# main.net
KiCad netlist of a schematic drawn in EAGLE
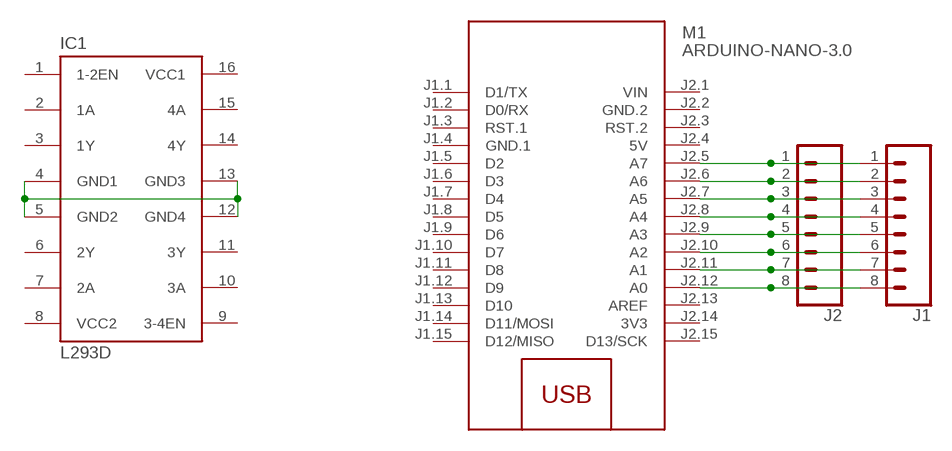
[diagram p0: schematic, sheet 1]

(export (version "E")
  (design (tool "Eeschema 10.0.6"))
  (components
    (comp (ref "IC1")
      (value "L293D")
      (footprint "eagle-import:DIL16")
      (libsource (lib "eagle-import") (part "L293D"))
    )
    (comp (ref "J1")
      (value "CONN_08LONGPADS")
      (footprint "eagle-import:1X08_LONGPADS")
      (libsource (lib "eagle-import") (part "CONN_08LONGPADS"))
    )
    (comp (ref "J2")
      (value "CONN_08LONGPADS")
      (footprint "eagle-import:1X08_LONGPADS")
      (libsource (lib "eagle-import") (part "CONN_08LONGPADS"))
    )
    (comp (ref "M1")
      (value "ARDUINO-NANO-3.0")
      (footprint "eagle-import:ARDUINO-NANO-3.0")
      (libsource (lib "eagle-import") (part "ARDUINO-NANO-3.0"))
    )
  )
  (nets
    (net (code "1") (name "/3V3") (class "Default")
      (node (ref "M1") (pin "J2.14") (pinfunction "3V3_J2.14") (pintype "power_in"))
    )
    (net (code "2") (name "/5V") (class "Default")
      (node (ref "M1") (pin "J2.4") (pinfunction "5V_J2.4") (pintype "power_in"))
    )
    (net (code "3") (name "/GND.1") (class "Default")
      (node (ref "M1") (pin "J1.4") (pinfunction "GND.1_J1.4") (pintype "power_in"))
    )
    (net (code "4") (name "/GND.2") (class "Default")
      (node (ref "M1") (pin "J2.2") (pinfunction "GND.2_J2.2") (pintype "power_in"))
    )
    (net (code "5") (name "/VCC1") (class "Default")
      (node (ref "IC1") (pin "16") (pinfunction "VCC1_16") (pintype "power_in"))
    )
    (net (code "6") (name "/VCC2") (class "Default")
      (node (ref "IC1") (pin "8") (pinfunction "VCC2_8") (pintype "power_in"))
    )
    (net (code "7") (name "/VIN") (class "Default")
      (node (ref "M1") (pin "J2.1") (pinfunction "VIN_J2.1") (pintype "power_in"))
    )
    (net (code "8") (name "Net-(IC1-GND1)") (class "Default")
      (node (ref "IC1") (pin "12") (pinfunction "GND4_12") (pintype "power_in"))
      (node (ref "IC1") (pin "13") (pinfunction "GND3_13") (pintype "power_in"))
      (node (ref "IC1") (pin "4") (pinfunction "GND1_4") (pintype "power_in"))
      (node (ref "IC1") (pin "5") (pinfunction "GND2_5") (pintype "power_in"))
    )
    (net (code "9") (name "Net-(M1-A0)") (class "Default")
      (node (ref "J1") (pin "8") (pinfunction "8_8") (pintype "passive"))
      (node (ref "J2") (pin "8") (pinfunction "8_8") (pintype "passive"))
      (node (ref "M1") (pin "J2.12") (pinfunction "A0_J2.12") (pintype "bidirectional"))
    )
    (net (code "10") (name "Net-(M1-A1)") (class "Default")
      (node (ref "J1") (pin "7") (pinfunction "7_7") (pintype "passive"))
      (node (ref "J2") (pin "7") (pinfunction "7_7") (pintype "passive"))
      (node (ref "M1") (pin "J2.11") (pinfunction "A1_J2.11") (pintype "bidirectional"))
    )
    (net (code "11") (name "Net-(M1-A2)") (class "Default")
      (node (ref "J1") (pin "6") (pinfunction "6_6") (pintype "passive"))
      (node (ref "J2") (pin "6") (pinfunction "6_6") (pintype "passive"))
      (node (ref "M1") (pin "J2.10") (pinfunction "A2_J2.10") (pintype "bidirectional"))
    )
    (net (code "12") (name "Net-(M1-A3)") (class "Default")
      (node (ref "J1") (pin "5") (pinfunction "5_5") (pintype "passive"))
      (node (ref "J2") (pin "5") (pinfunction "5_5") (pintype "passive"))
      (node (ref "M1") (pin "J2.9") (pinfunction "A3_J2.9") (pintype "bidirectional"))
    )
    (net (code "13") (name "Net-(M1-A4)") (class "Default")
      (node (ref "J1") (pin "4") (pinfunction "4_4") (pintype "passive"))
      (node (ref "J2") (pin "4") (pinfunction "4_4") (pintype "passive"))
      (node (ref "M1") (pin "J2.8") (pinfunction "A4_J2.8") (pintype "bidirectional"))
    )
    (net (code "14") (name "Net-(M1-A5)") (class "Default")
      (node (ref "J1") (pin "3") (pinfunction "3_3") (pintype "passive"))
      (node (ref "J2") (pin "3") (pinfunction "3_3") (pintype "passive"))
      (node (ref "M1") (pin "J2.7") (pinfunction "A5_J2.7") (pintype "bidirectional"))
    )
    (net (code "15") (name "Net-(M1-A6)") (class "Default")
      (node (ref "J1") (pin "2") (pinfunction "2_2") (pintype "passive"))
      (node (ref "J2") (pin "2") (pinfunction "2_2") (pintype "passive"))
      (node (ref "M1") (pin "J2.6") (pinfunction "A6_J2.6") (pintype "bidirectional"))
    )
    (net (code "16") (name "Net-(M1-A7)") (class "Default")
      (node (ref "J1") (pin "1") (pinfunction "1_1") (pintype "passive"))
      (node (ref "J2") (pin "1") (pinfunction "1_1") (pintype "passive"))
      (node (ref "M1") (pin "J2.5") (pinfunction "A7_J2.5") (pintype "bidirectional"))
    )
    (net (code "17") (name "unconnected-(IC1-1-2EN-Pad1)") (class "Default")
      (node (ref "IC1") (pin "1") (pinfunction "1-2EN_1") (pintype "input"))
    )
    (net (code "18") (name "unconnected-(IC1-1A-Pad2)") (class "Default")
      (node (ref "IC1") (pin "2") (pinfunction "1A_2") (pintype "input"))
    )
    (net (code "19") (name "unconnected-(IC1-1Y-Pad3)") (class "Default")
      (node (ref "IC1") (pin "3") (pinfunction "1Y_3") (pintype "output"))
    )
    (net (code "20") (name "unconnected-(IC1-2A-Pad7)") (class "Default")
      (node (ref "IC1") (pin "7") (pinfunction "2A_7") (pintype "input"))
    )
    (net (code "21") (name "unconnected-(IC1-2Y-Pad6)") (class "Default")
      (node (ref "IC1") (pin "6") (pinfunction "2Y_6") (pintype "output"))
    )
    (net (code "22") (name "unconnected-(IC1-3-4EN-Pad9)") (class "Default")
      (node (ref "IC1") (pin "9") (pinfunction "3-4EN_9") (pintype "input"))
    )
    (net (code "23") (name "unconnected-(IC1-3A-Pad10)") (class "Default")
      (node (ref "IC1") (pin "10") (pinfunction "3A_10") (pintype "input"))
    )
    (net (code "24") (name "unconnected-(IC1-3Y-Pad11)") (class "Default")
      (node (ref "IC1") (pin "11") (pinfunction "3Y_11") (pintype "output"))
    )
    (net (code "25") (name "unconnected-(IC1-4A-Pad15)") (class "Default")
      (node (ref "IC1") (pin "15") (pinfunction "4A_15") (pintype "input"))
    )
    (net (code "26") (name "unconnected-(IC1-4Y-Pad14)") (class "Default")
      (node (ref "IC1") (pin "14") (pinfunction "4Y_14") (pintype "output"))
    )
    (net (code "27") (name "unconnected-(M1-AREF-PadJ2.13)") (class "Default")
      (node (ref "M1") (pin "J2.13") (pinfunction "AREF_J2.13") (pintype "bidirectional"))
    )
    (net (code "28") (name "unconnected-(M1-D0{slash}RX-PadJ1.2)") (class "Default")
      (node (ref "M1") (pin "J1.2") (pinfunction "D0/RX_J1.2") (pintype "bidirectional"))
    )
    (net (code "29") (name "unconnected-(M1-D1{slash}TX-PadJ1.1)") (class "Default")
      (node (ref "M1") (pin "J1.1") (pinfunction "D1/TX_J1.1") (pintype "bidirectional"))
    )
    (net (code "30") (name "unconnected-(M1-D2-PadJ1.5)") (class "Default")
      (node (ref "M1") (pin "J1.5") (pinfunction "D2_J1.5") (pintype "bidirectional"))
    )
    (net (code "31") (name "unconnected-(M1-D3-PadJ1.6)") (class "Default")
      (node (ref "M1") (pin "J1.6") (pinfunction "D3_J1.6") (pintype "bidirectional"))
    )
    (net (code "32") (name "unconnected-(M1-D4-PadJ1.7)") (class "Default")
      (node (ref "M1") (pin "J1.7") (pinfunction "D4_J1.7") (pintype "bidirectional"))
    )
    (net (code "33") (name "unconnected-(M1-D5-PadJ1.8)") (class "Default")
      (node (ref "M1") (pin "J1.8") (pinfunction "D5_J1.8") (pintype "bidirectional"))
    )
    (net (code "34") (name "unconnected-(M1-D6-PadJ1.9)") (class "Default")
      (node (ref "M1") (pin "J1.9") (pinfunction "D6_J1.9") (pintype "bidirectional"))
    )
    (net (code "35") (name "unconnected-(M1-D7-PadJ1.10)") (class "Default")
      (node (ref "M1") (pin "J1.10") (pinfunction "D7_J1.10") (pintype "bidirectional"))
    )
    (net (code "36") (name "unconnected-(M1-D8-PadJ1.11)") (class "Default")
      (node (ref "M1") (pin "J1.11") (pinfunction "D8_J1.11") (pintype "bidirectional"))
    )
    (net (code "37") (name "unconnected-(M1-D9-PadJ1.12)") (class "Default")
      (node (ref "M1") (pin "J1.12") (pinfunction "D9_J1.12") (pintype "bidirectional"))
    )
    (net (code "38") (name "unconnected-(M1-D10-PadJ1.13)") (class "Default")
      (node (ref "M1") (pin "J1.13") (pinfunction "D10_J1.13") (pintype "bidirectional"))
    )
    (net (code "39") (name "unconnected-(M1-D11{slash}MOSI-PadJ1.14)") (class "Default")
      (node (ref "M1") (pin "J1.14") (pinfunction "D11/MOSI_J1.14") (pintype "bidirectional"))
    )
    (net (code "40") (name "unconnected-(M1-D12{slash}MISO-PadJ1.15)") (class "Default")
      (node (ref "M1") (pin "J1.15") (pinfunction "D12/MISO_J1.15") (pintype "bidirectional"))
    )
    (net (code "41") (name "unconnected-(M1-D13{slash}SCK-PadJ2.15)") (class "Default")
      (node (ref "M1") (pin "J2.15") (pinfunction "D13/SCK_J2.15") (pintype "bidirectional"))
    )
    (net (code "42") (name "unconnected-(M1-RST.1-PadJ1.3)") (class "Default")
      (node (ref "M1") (pin "J1.3") (pinfunction "RST.1_J1.3") (pintype "bidirectional"))
    )
    (net (code "43") (name "unconnected-(M1-RST.2-PadJ2.3)") (class "Default")
      (node (ref "M1") (pin "J2.3") (pinfunction "RST.2_J2.3") (pintype "bidirectional"))
    )
  )
)
